# Edge-Lit_Clock_v3_1.net
KiCad netlist of a schematic drawn in EAGLE
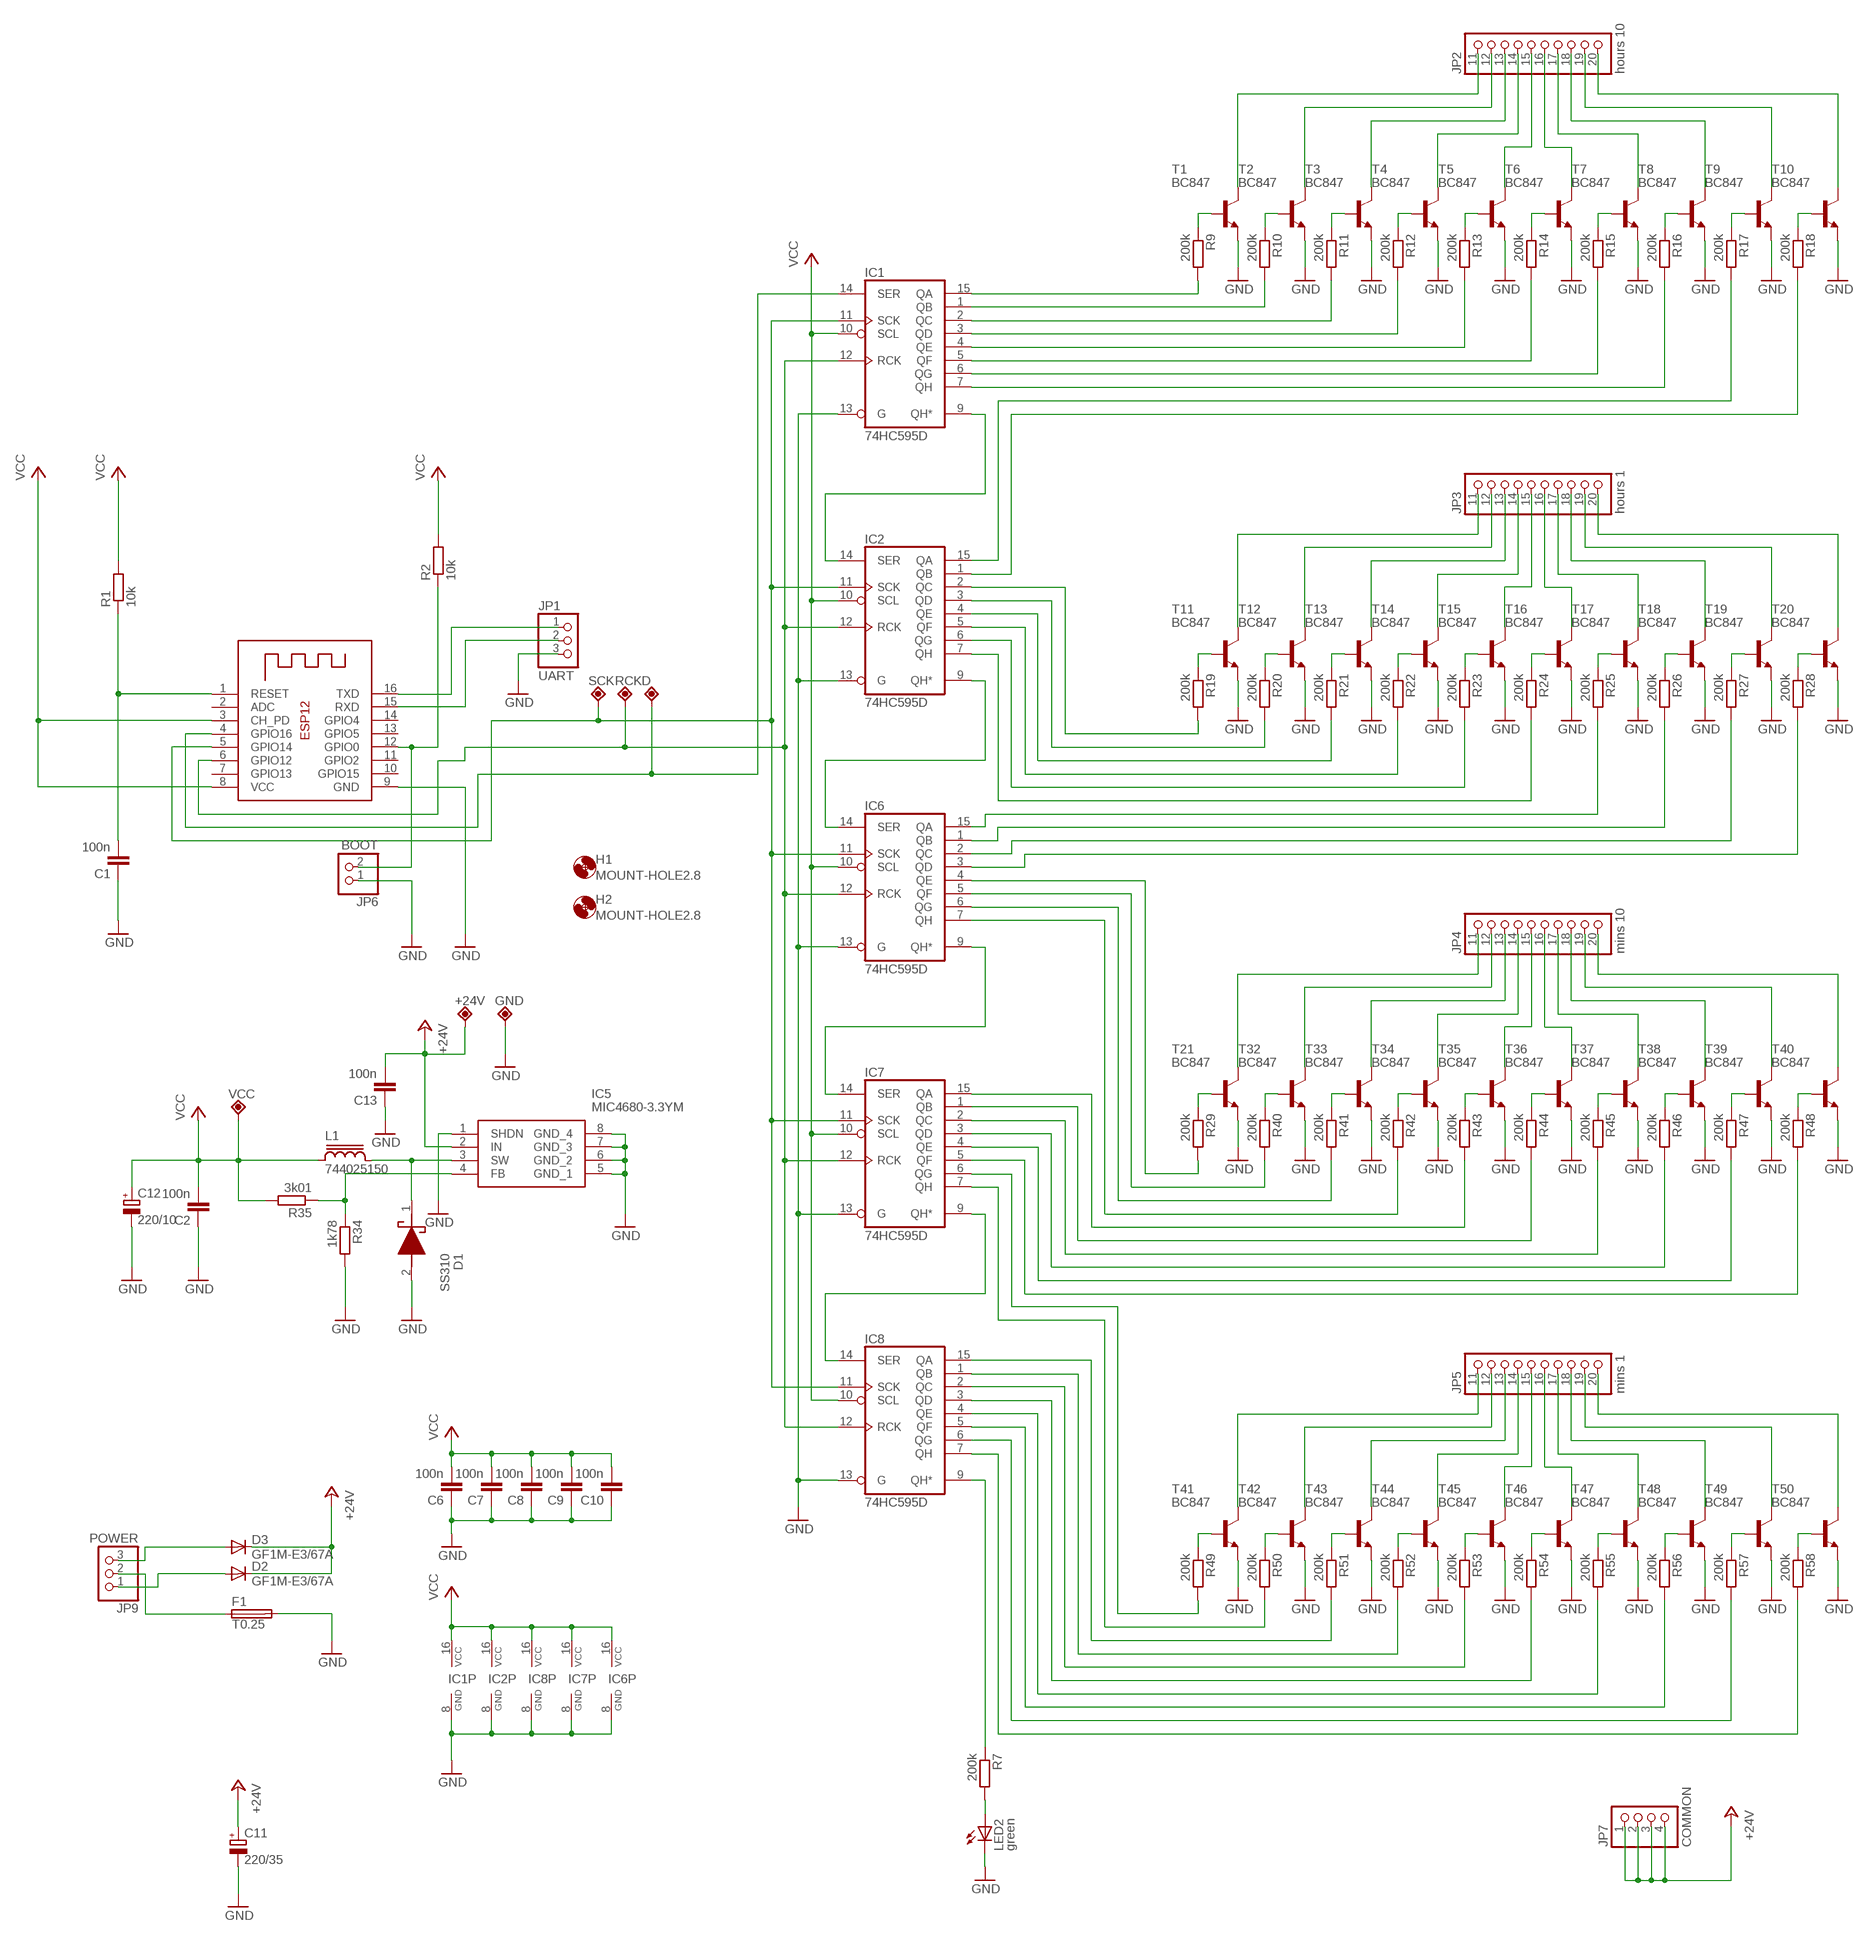
[diagram p0: schematic, sheet 1]

(export (version "E")
  (design (tool "Eeschema 10.0.6"))
  (components
    (comp (ref "+24V")
      (value "TPP-PAD-024")
      (footprint "eagle-import:PAD-024")
      (libsource (lib "eagle-import") (part "TPP-PAD-024"))
    )
    (comp (ref "C1")
      (value "100n")
      (footprint "eagle-import:C0805")
      (libsource (lib "eagle-import") (part "C-EUC0805"))
    )
    (comp (ref "C2")
      (value "100n")
      (footprint "eagle-import:C0805")
      (libsource (lib "eagle-import") (part "C-EUC0805"))
    )
    (comp (ref "C6")
      (value "100n")
      (footprint "eagle-import:C0805")
      (libsource (lib "eagle-import") (part "C-EUC0805"))
    )
    (comp (ref "C7")
      (value "100n")
      (footprint "eagle-import:C0805")
      (libsource (lib "eagle-import") (part "C-EUC0805"))
    )
    (comp (ref "C8")
      (value "100n")
      (footprint "eagle-import:C0805")
      (libsource (lib "eagle-import") (part "C-EUC0805"))
    )
    (comp (ref "C9")
      (value "100n")
      (footprint "eagle-import:C0805")
      (libsource (lib "eagle-import") (part "C-EUC0805"))
    )
    (comp (ref "C10")
      (value "100n")
      (footprint "eagle-import:C0805")
      (libsource (lib "eagle-import") (part "C-EUC0805"))
    )
    (comp (ref "C11")
      (value "220/35")
      (footprint "eagle-import:SANYO-OSCON_SMD_E7")
      (libsource (lib "eagle-import") (part "CPOL-EUSANYO_SMD_E7"))
    )
    (comp (ref "C12")
      (value "220/10")
      (footprint "eagle-import:SANYO-OSCON_SMD_E7")
      (libsource (lib "eagle-import") (part "CPOL-EUSANYO_SMD_E7"))
    )
    (comp (ref "C13")
      (value "100n")
      (footprint "eagle-import:C0805")
      (libsource (lib "eagle-import") (part "C-EUC0805"))
    )
    (comp (ref "D")
      (value "TPP-PAD-024")
      (footprint "eagle-import:PAD-024")
      (libsource (lib "eagle-import") (part "TPP-PAD-024"))
    )
    (comp (ref "D1")
      (value "SS310")
      (footprint "eagle-import:DIOM7959X262N")
      (fields (field (name "MOUSER_PART_NUMBER") "821-SS310"))
      (libsource (lib "eagle-import") (part "SS310"))
    )
    (comp (ref "D2")
      (value "GF1M-E3/67A")
      (footprint "eagle-import:DO214BA")
      (libsource (lib "eagle-import") (part "DIODE-DO214BA"))
    )
    (comp (ref "D3")
      (value "GF1M-E3/67A")
      (footprint "eagle-import:DO214BA")
      (libsource (lib "eagle-import") (part "DIODE-DO214BA"))
    )
    (comp (ref "F1")
      (value "T0.25")
      (footprint "eagle-import:TE5")
      (libsource (lib "eagle-import") (part "TE5"))
    )
    (comp (ref "GND")
      (value "TPP-PAD-024")
      (footprint "eagle-import:PAD-024")
      (libsource (lib "eagle-import") (part "TPP-PAD-024"))
    )
    (comp (ref "H1")
      (value "MOUNT-HOLE2.8")
      (footprint "eagle-import:2,8")
      (libsource (lib "eagle-import") (part "MOUNT-HOLE2.8"))
    )
    (comp (ref "H2")
      (value "MOUNT-HOLE2.8")
      (footprint "eagle-import:2,8")
      (libsource (lib "eagle-import") (part "MOUNT-HOLE2.8"))
    )
    (comp (ref "IC1")
      (value "74HC595D")
      (footprint "eagle-import:SO16")
      (libsource (lib "eagle-import") (part "74595DHC"))
    )
    (comp (ref "IC2")
      (value "74HC595D")
      (footprint "eagle-import:SO16")
      (libsource (lib "eagle-import") (part "74595DHC"))
    )
    (comp (ref "IC5")
      (value "MIC4680-3.3YM")
      (footprint "eagle-import:SOIC127P599X173-8N")
      (fields (field (name "MOUSER_PART_NUMBER") "998-MIC4680-3.3YM"))
      (libsource (lib "eagle-import") (part "MIC4680-3.3YM"))
    )
    (comp (ref "IC6")
      (value "74HC595D")
      (footprint "eagle-import:SO16")
      (libsource (lib "eagle-import") (part "74595DHC"))
    )
    (comp (ref "IC7")
      (value "74HC595D")
      (footprint "eagle-import:SO16")
      (libsource (lib "eagle-import") (part "74595DHC"))
    )
    (comp (ref "IC8")
      (value "74HC595D")
      (footprint "eagle-import:SO16")
      (libsource (lib "eagle-import") (part "74595DHC"))
    )
    (comp (ref "JP1")
      (value "UART")
      (footprint "eagle-import:1X03")
      (libsource (lib "eagle-import") (part "PINHD-1X3"))
    )
    (comp (ref "JP2")
      (value "hours 10")
      (footprint "eagle-import:1X10")
      (libsource (lib "eagle-import") (part "PINHD-1X10"))
    )
    (comp (ref "JP3")
      (value "hours 1")
      (footprint "eagle-import:1X10")
      (libsource (lib "eagle-import") (part "PINHD-1X10"))
    )
    (comp (ref "JP4")
      (value "mins 10")
      (footprint "eagle-import:1X10")
      (libsource (lib "eagle-import") (part "PINHD-1X10"))
    )
    (comp (ref "JP5")
      (value "mins 1")
      (footprint "eagle-import:1X10")
      (libsource (lib "eagle-import") (part "PINHD-1X10"))
    )
    (comp (ref "JP6")
      (value "BOOT")
      (footprint "eagle-import:1X02")
      (libsource (lib "eagle-import") (part "PINHD-1X2"))
    )
    (comp (ref "JP7")
      (value "COMMON")
      (footprint "eagle-import:1X04")
      (libsource (lib "eagle-import") (part "PINHD-1X4"))
    )
    (comp (ref "JP9")
      (value "POWER")
      (footprint "eagle-import:1X03")
      (libsource (lib "eagle-import") (part "PINHD-1X3"))
    )
    (comp (ref "L1")
      (value "744025150")
      (footprint "eagle-import:744025150")
      (libsource (lib "eagle-import") (part "744025150"))
    )
    (comp (ref "LED2")
      (value "green")
      (footprint "eagle-import:SML0805")
      (libsource (lib "eagle-import") (part "LEDSML0805"))
    )
    (comp (ref "R1")
      (value "10k")
      (footprint "eagle-import:M0805")
      (libsource (lib "eagle-import") (part "R-EU_M0805"))
    )
    (comp (ref "R2")
      (value "10k")
      (footprint "eagle-import:M0805")
      (libsource (lib "eagle-import") (part "R-EU_M0805"))
    )
    (comp (ref "R7")
      (value "200k")
      (footprint "eagle-import:M0805")
      (libsource (lib "eagle-import") (part "R-EU_M0805"))
    )
    (comp (ref "R9")
      (value "200k")
      (footprint "eagle-import:M0805")
      (libsource (lib "eagle-import") (part "R-EU_M0805"))
    )
    (comp (ref "R10")
      (value "200k")
      (footprint "eagle-import:M0805")
      (libsource (lib "eagle-import") (part "R-EU_M0805"))
    )
    (comp (ref "R11")
      (value "200k")
      (footprint "eagle-import:M0805")
      (libsource (lib "eagle-import") (part "R-EU_M0805"))
    )
    (comp (ref "R12")
      (value "200k")
      (footprint "eagle-import:M0805")
      (libsource (lib "eagle-import") (part "R-EU_M0805"))
    )
    (comp (ref "R13")
      (value "200k")
      (footprint "eagle-import:M0805")
      (libsource (lib "eagle-import") (part "R-EU_M0805"))
    )
    (comp (ref "R14")
      (value "200k")
      (footprint "eagle-import:M0805")
      (libsource (lib "eagle-import") (part "R-EU_M0805"))
    )
    (comp (ref "R15")
      (value "200k")
      (footprint "eagle-import:M0805")
      (libsource (lib "eagle-import") (part "R-EU_M0805"))
    )
    (comp (ref "R16")
      (value "200k")
      (footprint "eagle-import:M0805")
      (libsource (lib "eagle-import") (part "R-EU_M0805"))
    )
    (comp (ref "R17")
      (value "200k")
      (footprint "eagle-import:M0805")
      (libsource (lib "eagle-import") (part "R-EU_M0805"))
    )
    (comp (ref "R18")
      (value "200k")
      (footprint "eagle-import:M0805")
      (libsource (lib "eagle-import") (part "R-EU_M0805"))
    )
    (comp (ref "R19")
      (value "200k")
      (footprint "eagle-import:M0805")
      (libsource (lib "eagle-import") (part "R-EU_M0805"))
    )
    (comp (ref "R20")
      (value "200k")
      (footprint "eagle-import:M0805")
      (libsource (lib "eagle-import") (part "R-EU_M0805"))
    )
    (comp (ref "R21")
      (value "200k")
      (footprint "eagle-import:M0805")
      (libsource (lib "eagle-import") (part "R-EU_M0805"))
    )
    (comp (ref "R22")
      (value "200k")
      (footprint "eagle-import:M0805")
      (libsource (lib "eagle-import") (part "R-EU_M0805"))
    )
    (comp (ref "R23")
      (value "200k")
      (footprint "eagle-import:M0805")
      (libsource (lib "eagle-import") (part "R-EU_M0805"))
    )
    (comp (ref "R24")
      (value "200k")
      (footprint "eagle-import:M0805")
      (libsource (lib "eagle-import") (part "R-EU_M0805"))
    )
    (comp (ref "R25")
      (value "200k")
      (footprint "eagle-import:M0805")
      (libsource (lib "eagle-import") (part "R-EU_M0805"))
    )
    (comp (ref "R26")
      (value "200k")
      (footprint "eagle-import:M0805")
      (libsource (lib "eagle-import") (part "R-EU_M0805"))
    )
    (comp (ref "R27")
      (value "200k")
      (footprint "eagle-import:M0805")
      (libsource (lib "eagle-import") (part "R-EU_M0805"))
    )
    (comp (ref "R28")
      (value "200k")
      (footprint "eagle-import:M0805")
      (libsource (lib "eagle-import") (part "R-EU_M0805"))
    )
    (comp (ref "R29")
      (value "200k")
      (footprint "eagle-import:M0805")
      (libsource (lib "eagle-import") (part "R-EU_M0805"))
    )
    (comp (ref "R34")
      (value "1k78")
      (footprint "eagle-import:M0805")
      (libsource (lib "eagle-import") (part "R-EU_M0805"))
    )
    (comp (ref "R35")
      (value "3k01")
      (footprint "eagle-import:M0805")
      (libsource (lib "eagle-import") (part "R-EU_M0805"))
    )
    (comp (ref "R40")
      (value "200k")
      (footprint "eagle-import:M0805")
      (libsource (lib "eagle-import") (part "R-EU_M0805"))
    )
    (comp (ref "R41")
      (value "200k")
      (footprint "eagle-import:M0805")
      (libsource (lib "eagle-import") (part "R-EU_M0805"))
    )
    (comp (ref "R42")
      (value "200k")
      (footprint "eagle-import:M0805")
      (libsource (lib "eagle-import") (part "R-EU_M0805"))
    )
    (comp (ref "R43")
      (value "200k")
      (footprint "eagle-import:M0805")
      (libsource (lib "eagle-import") (part "R-EU_M0805"))
    )
    (comp (ref "R44")
      (value "200k")
      (footprint "eagle-import:M0805")
      (libsource (lib "eagle-import") (part "R-EU_M0805"))
    )
    (comp (ref "R45")
      (value "200k")
      (footprint "eagle-import:M0805")
      (libsource (lib "eagle-import") (part "R-EU_M0805"))
    )
    (comp (ref "R46")
      (value "200k")
      (footprint "eagle-import:M0805")
      (libsource (lib "eagle-import") (part "R-EU_M0805"))
    )
    (comp (ref "R47")
      (value "200k")
      (footprint "eagle-import:M0805")
      (libsource (lib "eagle-import") (part "R-EU_M0805"))
    )
    (comp (ref "R48")
      (value "200k")
      (footprint "eagle-import:M0805")
      (libsource (lib "eagle-import") (part "R-EU_M0805"))
    )
    (comp (ref "R49")
      (value "200k")
      (footprint "eagle-import:M0805")
      (libsource (lib "eagle-import") (part "R-EU_M0805"))
    )
    (comp (ref "R50")
      (value "200k")
      (footprint "eagle-import:M0805")
      (libsource (lib "eagle-import") (part "R-EU_M0805"))
    )
    (comp (ref "R51")
      (value "200k")
      (footprint "eagle-import:M0805")
      (libsource (lib "eagle-import") (part "R-EU_M0805"))
    )
    (comp (ref "R52")
      (value "200k")
      (footprint "eagle-import:M0805")
      (libsource (lib "eagle-import") (part "R-EU_M0805"))
    )
    (comp (ref "R53")
      (value "200k")
      (footprint "eagle-import:M0805")
      (libsource (lib "eagle-import") (part "R-EU_M0805"))
    )
    (comp (ref "R54")
      (value "200k")
      (footprint "eagle-import:M0805")
      (libsource (lib "eagle-import") (part "R-EU_M0805"))
    )
    (comp (ref "R55")
      (value "200k")
      (footprint "eagle-import:M0805")
      (libsource (lib "eagle-import") (part "R-EU_M0805"))
    )
    (comp (ref "R56")
      (value "200k")
      (footprint "eagle-import:M0805")
      (libsource (lib "eagle-import") (part "R-EU_M0805"))
    )
    (comp (ref "R57")
      (value "200k")
      (footprint "eagle-import:M0805")
      (libsource (lib "eagle-import") (part "R-EU_M0805"))
    )
    (comp (ref "R58")
      (value "200k")
      (footprint "eagle-import:M0805")
      (libsource (lib "eagle-import") (part "R-EU_M0805"))
    )
    (comp (ref "RCK")
      (value "TPP-PAD-024")
      (footprint "eagle-import:PAD-024")
      (libsource (lib "eagle-import") (part "TPP-PAD-024"))
    )
    (comp (ref "SCK")
      (value "TPP-PAD-024")
      (footprint "eagle-import:PAD-024")
      (libsource (lib "eagle-import") (part "TPP-PAD-024"))
    )
    (comp (ref "T1")
      (value "BC847")
      (footprint "eagle-import:SOT23")
      (libsource (lib "eagle-import") (part "BC847"))
    )
    (comp (ref "T2")
      (value "BC847")
      (footprint "eagle-import:SOT23")
      (libsource (lib "eagle-import") (part "BC847"))
    )
    (comp (ref "T3")
      (value "BC847")
      (footprint "eagle-import:SOT23")
      (libsource (lib "eagle-import") (part "BC847"))
    )
    (comp (ref "T4")
      (value "BC847")
      (footprint "eagle-import:SOT23")
      (libsource (lib "eagle-import") (part "BC847"))
    )
    (comp (ref "T5")
      (value "BC847")
      (footprint "eagle-import:SOT23")
      (libsource (lib "eagle-import") (part "BC847"))
    )
    (comp (ref "T6")
      (value "BC847")
      (footprint "eagle-import:SOT23")
      (libsource (lib "eagle-import") (part "BC847"))
    )
    (comp (ref "T7")
      (value "BC847")
      (footprint "eagle-import:SOT23")
      (libsource (lib "eagle-import") (part "BC847"))
    )
    (comp (ref "T8")
      (value "BC847")
      (footprint "eagle-import:SOT23")
      (libsource (lib "eagle-import") (part "BC847"))
    )
    (comp (ref "T9")
      (value "BC847")
      (footprint "eagle-import:SOT23")
      (libsource (lib "eagle-import") (part "BC847"))
    )
    (comp (ref "T10")
      (value "BC847")
      (footprint "eagle-import:SOT23")
      (libsource (lib "eagle-import") (part "BC847"))
    )
    (comp (ref "T11")
      (value "BC847")
      (footprint "eagle-import:SOT23")
      (libsource (lib "eagle-import") (part "BC847"))
    )
    (comp (ref "T12")
      (value "BC847")
      (footprint "eagle-import:SOT23")
      (libsource (lib "eagle-import") (part "BC847"))
    )
    (comp (ref "T13")
      (value "BC847")
      (footprint "eagle-import:SOT23")
      (libsource (lib "eagle-import") (part "BC847"))
    )
    (comp (ref "T14")
      (value "BC847")
      (footprint "eagle-import:SOT23")
      (libsource (lib "eagle-import") (part "BC847"))
    )
    (comp (ref "T15")
      (value "BC847")
      (footprint "eagle-import:SOT23")
      (libsource (lib "eagle-import") (part "BC847"))
    )
    (comp (ref "T16")
      (value "BC847")
      (footprint "eagle-import:SOT23")
      (libsource (lib "eagle-import") (part "BC847"))
    )
    (comp (ref "T17")
      (value "BC847")
      (footprint "eagle-import:SOT23")
      (libsource (lib "eagle-import") (part "BC847"))
    )
    (comp (ref "T18")
      (value "BC847")
      (footprint "eagle-import:SOT23")
      (libsource (lib "eagle-import") (part "BC847"))
    )
    (comp (ref "T19")
      (value "BC847")
      (footprint "eagle-import:SOT23")
      (libsource (lib "eagle-import") (part "BC847"))
    )
    (comp (ref "T20")
      (value "BC847")
      (footprint "eagle-import:SOT23")
      (libsource (lib "eagle-import") (part "BC847"))
    )
    (comp (ref "T21")
      (value "BC847")
      (footprint "eagle-import:SOT23")
      (libsource (lib "eagle-import") (part "BC847"))
    )
    (comp (ref "T32")
      (value "BC847")
      (footprint "eagle-import:SOT23")
      (libsource (lib "eagle-import") (part "BC847"))
    )
    (comp (ref "T33")
      (value "BC847")
      (footprint "eagle-import:SOT23")
      (libsource (lib "eagle-import") (part "BC847"))
    )
    (comp (ref "T34")
      (value "BC847")
      (footprint "eagle-import:SOT23")
      (libsource (lib "eagle-import") (part "BC847"))
    )
    (comp (ref "T35")
      (value "BC847")
      (footprint "eagle-import:SOT23")
      (libsource (lib "eagle-import") (part "BC847"))
    )
    (comp (ref "T36")
      (value "BC847")
      (footprint "eagle-import:SOT23")
      (libsource (lib "eagle-import") (part "BC847"))
    )
    (comp (ref "T37")
      (value "BC847")
      (footprint "eagle-import:SOT23")
      (libsource (lib "eagle-import") (part "BC847"))
    )
    (comp (ref "T38")
      (value "BC847")
      (footprint "eagle-import:SOT23")
      (libsource (lib "eagle-import") (part "BC847"))
    )
    (comp (ref "T39")
      (value "BC847")
      (footprint "eagle-import:SOT23")
      (libsource (lib "eagle-import") (part "BC847"))
    )
    (comp (ref "T40")
      (value "BC847")
      (footprint "eagle-import:SOT23")
      (libsource (lib "eagle-import") (part "BC847"))
    )
    (comp (ref "T41")
      (value "BC847")
      (footprint "eagle-import:SOT23")
      (libsource (lib "eagle-import") (part "BC847"))
    )
    (comp (ref "T42")
      (value "BC847")
      (footprint "eagle-import:SOT23")
      (libsource (lib "eagle-import") (part "BC847"))
    )
    (comp (ref "T43")
      (value "BC847")
      (footprint "eagle-import:SOT23")
      (libsource (lib "eagle-import") (part "BC847"))
    )
    (comp (ref "T44")
      (value "BC847")
      (footprint "eagle-import:SOT23")
      (libsource (lib "eagle-import") (part "BC847"))
    )
    (comp (ref "T45")
      (value "BC847")
      (footprint "eagle-import:SOT23")
      (libsource (lib "eagle-import") (part "BC847"))
    )
    (comp (ref "T46")
      (value "BC847")
      (footprint "eagle-import:SOT23")
      (libsource (lib "eagle-import") (part "BC847"))
    )
    (comp (ref "T47")
      (value "BC847")
      (footprint "eagle-import:SOT23")
      (libsource (lib "eagle-import") (part "BC847"))
    )
    (comp (ref "T48")
      (value "BC847")
      (footprint "eagle-import:SOT23")
      (libsource (lib "eagle-import") (part "BC847"))
    )
    (comp (ref "T49")
      (value "BC847")
      (footprint "eagle-import:SOT23")
      (libsource (lib "eagle-import") (part "BC847"))
    )
    (comp (ref "T50")
      (value "BC847")
      (footprint "eagle-import:SOT23")
      (libsource (lib "eagle-import") (part "BC847"))
    )
    (comp (ref "VCC")
      (value "TPP-PAD-024")
      (footprint "eagle-import:PAD-024")
      (libsource (lib "eagle-import") (part "TPP-PAD-024"))
    )
    (comp (ref "X1")
      (value "ESP12")
      (footprint "eagle-import:ESP-12")
      (libsource (lib "eagle-import") (part "ESP-12"))
    )
  )
  (nets
    (net (code "1") (name "+24V") (class "Default")
      (node (ref "+24V") (pin "1") (pinfunction "P_1") (pintype "passive"))
      (node (ref "C11") (pin "+") (pinfunction "+_+") (pintype "passive"))
      (node (ref "C13") (pin "2") (pinfunction "2_2") (pintype "passive"))
      (node (ref "D2") (pin "C") (pinfunction "C_C") (pintype "passive"))
      (node (ref "D3") (pin "C") (pinfunction "C_C") (pintype "passive"))
      (node (ref "IC5") (pin "2") (pinfunction "IN_2") (pintype "bidirectional"))
      (node (ref "JP7") (pin "1") (pinfunction "1_1") (pintype "passive"))
      (node (ref "JP7") (pin "2") (pinfunction "2_2") (pintype "passive"))
      (node (ref "JP7") (pin "3") (pinfunction "3_3") (pintype "passive"))
      (node (ref "JP7") (pin "4") (pinfunction "4_4") (pintype "passive"))
    )
    (net (code "2") (name "GND") (class "Default")
      (node (ref "C1") (pin "1") (pinfunction "1_1") (pintype "passive"))
      (node (ref "C10") (pin "1") (pinfunction "1_1") (pintype "passive"))
      (node (ref "C11") (pin "-") (pinfunction "-_-") (pintype "passive"))
      (node (ref "C12") (pin "-") (pinfunction "-_-") (pintype "passive"))
      (node (ref "C13") (pin "1") (pinfunction "1_1") (pintype "passive"))
      (node (ref "C2") (pin "1") (pinfunction "1_1") (pintype "passive"))
      (node (ref "C6") (pin "1") (pinfunction "1_1") (pintype "passive"))
      (node (ref "C7") (pin "1") (pinfunction "1_1") (pintype "passive"))
      (node (ref "C8") (pin "1") (pinfunction "1_1") (pintype "passive"))
      (node (ref "C9") (pin "1") (pinfunction "1_1") (pintype "passive"))
      (node (ref "D1") (pin "2") (pinfunction "A_2") (pintype "bidirectional"))
      (node (ref "F1") (pin "2") (pinfunction "2_2") (pintype "passive"))
      (node (ref "GND") (pin "1") (pinfunction "P_1") (pintype "passive"))
      (node (ref "IC1") (pin "13") (pinfunction "G_13") (pintype "input"))
      (node (ref "IC1") (pin "8") (pinfunction "GND_8") (pintype "power_in"))
      (node (ref "IC2") (pin "13") (pinfunction "G_13") (pintype "input"))
      (node (ref "IC2") (pin "8") (pinfunction "GND_8") (pintype "power_in"))
      (node (ref "IC5") (pin "1") (pinfunction "SHDN_1") (pintype "bidirectional"))
      (node (ref "IC5") (pin "5") (pinfunction "GND_1_5") (pintype "bidirectional"))
      (node (ref "IC5") (pin "6") (pinfunction "GND_2_6") (pintype "bidirectional"))
      (node (ref "IC5") (pin "7") (pinfunction "GND_3_7") (pintype "bidirectional"))
      (node (ref "IC5") (pin "8") (pinfunction "GND_4_8") (pintype "bidirectional"))
      (node (ref "IC6") (pin "13") (pinfunction "G_13") (pintype "input"))
      (node (ref "IC6") (pin "8") (pinfunction "GND_8") (pintype "power_in"))
      (node (ref "IC7") (pin "13") (pinfunction "G_13") (pintype "input"))
      (node (ref "IC7") (pin "8") (pinfunction "GND_8") (pintype "power_in"))
      (node (ref "IC8") (pin "13") (pinfunction "G_13") (pintype "input"))
      (node (ref "IC8") (pin "8") (pinfunction "GND_8") (pintype "power_in"))
      (node (ref "JP1") (pin "3") (pinfunction "3_3") (pintype "passive"))
      (node (ref "JP6") (pin "1") (pinfunction "1_1") (pintype "passive"))
      (node (ref "LED2") (pin "C") (pinfunction "C_C") (pintype "passive"))
      (node (ref "R34") (pin "2") (pinfunction "2_2") (pintype "passive"))
      (node (ref "T1") (pin "2") (pinfunction "E_2") (pintype "passive"))
      (node (ref "T10") (pin "2") (pinfunction "E_2") (pintype "passive"))
      (node (ref "T11") (pin "2") (pinfunction "E_2") (pintype "passive"))
      (node (ref "T12") (pin "2") (pinfunction "E_2") (pintype "passive"))
      (node (ref "T13") (pin "2") (pinfunction "E_2") (pintype "passive"))
      (node (ref "T14") (pin "2") (pinfunction "E_2") (pintype "passive"))
      (node (ref "T15") (pin "2") (pinfunction "E_2") (pintype "passive"))
      (node (ref "T16") (pin "2") (pinfunction "E_2") (pintype "passive"))
      (node (ref "T17") (pin "2") (pinfunction "E_2") (pintype "passive"))
      (node (ref "T18") (pin "2") (pinfunction "E_2") (pintype "passive"))
      (node (ref "T19") (pin "2") (pinfunction "E_2") (pintype "passive"))
      (node (ref "T2") (pin "2") (pinfunction "E_2") (pintype "passive"))
      (node (ref "T20") (pin "2") (pinfunction "E_2") (pintype "passive"))
      (node (ref "T21") (pin "2") (pinfunction "E_2") (pintype "passive"))
      (node (ref "T3") (pin "2") (pinfunction "E_2") (pintype "passive"))
      (node (ref "T32") (pin "2") (pinfunction "E_2") (pintype "passive"))
      (node (ref "T33") (pin "2") (pinfunction "E_2") (pintype "passive"))
      (node (ref "T34") (pin "2") (pinfunction "E_2") (pintype "passive"))
      (node (ref "T35") (pin "2") (pinfunction "E_2") (pintype "passive"))
      (node (ref "T36") (pin "2") (pinfunction "E_2") (pintype "passive"))
      (node (ref "T37") (pin "2") (pinfunction "E_2") (pintype "passive"))
      (node (ref "T38") (pin "2") (pinfunction "E_2") (pintype "passive"))
      (node (ref "T39") (pin "2") (pinfunction "E_2") (pintype "passive"))
      (node (ref "T4") (pin "2") (pinfunction "E_2") (pintype "passive"))
      (node (ref "T40") (pin "2") (pinfunction "E_2") (pintype "passive"))
      (node (ref "T41") (pin "2") (pinfunction "E_2") (pintype "passive"))
      (node (ref "T42") (pin "2") (pinfunction "E_2") (pintype "passive"))
      (node (ref "T43") (pin "2") (pinfunction "E_2") (pintype "passive"))
      (node (ref "T44") (pin "2") (pinfunction "E_2") (pintype "passive"))
      (node (ref "T45") (pin "2") (pinfunction "E_2") (pintype "passive"))
      (node (ref "T46") (pin "2") (pinfunction "E_2") (pintype "passive"))
      (node (ref "T47") (pin "2") (pinfunction "E_2") (pintype "passive"))
      (node (ref "T48") (pin "2") (pinfunction "E_2") (pintype "passive"))
      (node (ref "T49") (pin "2") (pinfunction "E_2") (pintype "passive"))
      (node (ref "T5") (pin "2") (pinfunction "E_2") (pintype "passive"))
      (node (ref "T50") (pin "2") (pinfunction "E_2") (pintype "passive"))
      (node (ref "T6") (pin "2") (pinfunction "E_2") (pintype "passive"))
      (node (ref "T7") (pin "2") (pinfunction "E_2") (pintype "passive"))
      (node (ref "T8") (pin "2") (pinfunction "E_2") (pintype "passive"))
      (node (ref "T9") (pin "2") (pinfunction "E_2") (pintype "passive"))
      (node (ref "X1") (pin "9") (pinfunction "GND_9") (pintype "power_in"))
    )
    (net (code "3") (name "Net-(D-P)") (class "Default")
      (node (ref "D") (pin "1") (pinfunction "P_1") (pintype "passive"))
      (node (ref "IC1") (pin "14") (pinfunction "SER_14") (pintype "input"))
      (node (ref "X1") (pin "4") (pinfunction "GPIO16_4") (pintype "bidirectional"))
    )
    (net (code "4") (name "Net-(D1-K)") (class "Default")
      (node (ref "D1") (pin "1") (pinfunction "K_1") (pintype "bidirectional"))
      (node (ref "IC5") (pin "3") (pinfunction "SW_3") (pintype "bidirectional"))
      (node (ref "L1") (pin "2") (pinfunction "2_2") (pintype "passive"))
    )
    (net (code "5") (name "Net-(D2-PadA)") (class "Default")
      (node (ref "D2") (pin "A") (pinfunction "A_A") (pintype "passive"))
      (node (ref "JP9") (pin "1") (pinfunction "1_1") (pintype "passive"))
    )
    (net (code "6") (name "Net-(D3-PadA)") (class "Default")
      (node (ref "D3") (pin "A") (pinfunction "A_A") (pintype "passive"))
      (node (ref "JP9") (pin "3") (pinfunction "3_3") (pintype "passive"))
    )
    (net (code "7") (name "Net-(F1-Pad1)") (class "Default")
      (node (ref "F1") (pin "1") (pinfunction "1_1") (pintype "passive"))
      (node (ref "JP9") (pin "2") (pinfunction "2_2") (pintype "passive"))
    )
    (net (code "8") (name "Net-(IC1A-QA)") (class "Default")
      (node (ref "IC1") (pin "15") (pinfunction "QA_15") (pintype "tri_state"))
      (node (ref "R9") (pin "2") (pinfunction "2_2") (pintype "passive"))
    )
    (net (code "9") (name "Net-(IC1A-QB)") (class "Default")
      (node (ref "IC1") (pin "1") (pinfunction "QB_1") (pintype "tri_state"))
      (node (ref "R10") (pin "2") (pinfunction "2_2") (pintype "passive"))
    )
    (net (code "10") (name "Net-(IC1A-QC)") (class "Default")
      (node (ref "IC1") (pin "2") (pinfunction "QC_2") (pintype "tri_state"))
      (node (ref "R11") (pin "2") (pinfunction "2_2") (pintype "passive"))
    )
    (net (code "11") (name "Net-(IC1A-QD)") (class "Default")
      (node (ref "IC1") (pin "3") (pinfunction "QD_3") (pintype "tri_state"))
      (node (ref "R12") (pin "2") (pinfunction "2_2") (pintype "passive"))
    )
    (net (code "12") (name "Net-(IC1A-QE)") (class "Default")
      (node (ref "IC1") (pin "4") (pinfunction "QE_4") (pintype "tri_state"))
      (node (ref "R13") (pin "2") (pinfunction "2_2") (pintype "passive"))
    )
    (net (code "13") (name "Net-(IC1A-QF)") (class "Default")
      (node (ref "IC1") (pin "5") (pinfunction "QF_5") (pintype "tri_state"))
      (node (ref "R14") (pin "2") (pinfunction "2_2") (pintype "passive"))
    )
    (net (code "14") (name "Net-(IC1A-QG)") (class "Default")
      (node (ref "IC1") (pin "6") (pinfunction "QG_6") (pintype "tri_state"))
      (node (ref "R15") (pin "2") (pinfunction "2_2") (pintype "passive"))
    )
    (net (code "15") (name "Net-(IC1A-QH)") (class "Default")
      (node (ref "IC1") (pin "7") (pinfunction "QH_7") (pintype "tri_state"))
      (node (ref "R16") (pin "2") (pinfunction "2_2") (pintype "passive"))
    )
    (net (code "16") (name "Net-(IC1A-QH*)") (class "Default")
      (node (ref "IC1") (pin "9") (pinfunction "QH*_9") (pintype "tri_state"))
      (node (ref "IC2") (pin "14") (pinfunction "SER_14") (pintype "input"))
    )
    (net (code "17") (name "Net-(IC1A-RCK)") (class "Default")
      (node (ref "IC1") (pin "12") (pinfunction "RCK_12") (pintype "input"))
      (node (ref "IC2") (pin "12") (pinfunction "RCK_12") (pintype "input"))
      (node (ref "IC6") (pin "12") (pinfunction "RCK_12") (pintype "input"))
      (node (ref "IC7") (pin "12") (pinfunction "RCK_12") (pintype "input"))
      (node (ref "IC8") (pin "12") (pinfunction "RCK_12") (pintype "input"))
      (node (ref "RCK") (pin "1") (pinfunction "P_1") (pintype "passive"))
      (node (ref "X1") (pin "6") (pinfunction "GPIO12_6") (pintype "bidirectional"))
    )
    (net (code "18") (name "Net-(IC1A-SCK)") (class "Default")
      (node (ref "IC1") (pin "11") (pinfunction "SCK_11") (pintype "input"))
      (node (ref "IC2") (pin "11") (pinfunction "SCK_11") (pintype "input"))
      (node (ref "IC6") (pin "11") (pinfunction "SCK_11") (pintype "input"))
      (node (ref "IC7") (pin "11") (pinfunction "SCK_11") (pintype "input"))
      (node (ref "IC8") (pin "11") (pinfunction "SCK_11") (pintype "input"))
      (node (ref "SCK") (pin "1") (pinfunction "P_1") (pintype "passive"))
      (node (ref "X1") (pin "5") (pinfunction "GPIO14_5") (pintype "bidirectional"))
    )
    (net (code "19") (name "Net-(IC2A-QA)") (class "Default")
      (node (ref "IC2") (pin "15") (pinfunction "QA_15") (pintype "tri_state"))
      (node (ref "R17") (pin "2") (pinfunction "2_2") (pintype "passive"))
    )
    (net (code "20") (name "Net-(IC2A-QB)") (class "Default")
      (node (ref "IC2") (pin "1") (pinfunction "QB_1") (pintype "tri_state"))
      (node (ref "R18") (pin "2") (pinfunction "2_2") (pintype "passive"))
    )
    (net (code "21") (name "Net-(IC2A-QC)") (class "Default")
      (node (ref "IC2") (pin "2") (pinfunction "QC_2") (pintype "tri_state"))
      (node (ref "R19") (pin "2") (pinfunction "2_2") (pintype "passive"))
    )
    (net (code "22") (name "Net-(IC2A-QD)") (class "Default")
      (node (ref "IC2") (pin "3") (pinfunction "QD_3") (pintype "tri_state"))
      (node (ref "R20") (pin "2") (pinfunction "2_2") (pintype "passive"))
    )
    (net (code "23") (name "Net-(IC2A-QE)") (class "Default")
      (node (ref "IC2") (pin "4") (pinfunction "QE_4") (pintype "tri_state"))
      (node (ref "R21") (pin "2") (pinfunction "2_2") (pintype "passive"))
    )
    (net (code "24") (name "Net-(IC2A-QF)") (class "Default")
      (node (ref "IC2") (pin "5") (pinfunction "QF_5") (pintype "tri_state"))
      (node (ref "R22") (pin "2") (pinfunction "2_2") (pintype "passive"))
    )
    (net (code "25") (name "Net-(IC2A-QG)") (class "Default")
      (node (ref "IC2") (pin "6") (pinfunction "QG_6") (pintype "tri_state"))
      (node (ref "R23") (pin "2") (pinfunction "2_2") (pintype "passive"))
    )
    (net (code "26") (name "Net-(IC2A-QH)") (class "Default")
      (node (ref "IC2") (pin "7") (pinfunction "QH_7") (pintype "tri_state"))
      (node (ref "R24") (pin "2") (pinfunction "2_2") (pintype "passive"))
    )
    (net (code "27") (name "Net-(IC2A-QH*)") (class "Default")
      (node (ref "IC2") (pin "9") (pinfunction "QH*_9") (pintype "tri_state"))
      (node (ref "IC6") (pin "14") (pinfunction "SER_14") (pintype "input"))
    )
    (net (code "28") (name "Net-(IC5-FB)") (class "Default")
      (node (ref "IC5") (pin "4") (pinfunction "FB_4") (pintype "bidirectional"))
      (node (ref "R34") (pin "1") (pinfunction "1_1") (pintype "passive"))
      (node (ref "R35") (pin "1") (pinfunction "1_1") (pintype "passive"))
    )
    (net (code "29") (name "Net-(IC6A-QA)") (class "Default")
      (node (ref "IC6") (pin "15") (pinfunction "QA_15") (pintype "tri_state"))
      (node (ref "R25") (pin "2") (pinfunction "2_2") (pintype "passive"))
    )
    (net (code "30") (name "Net-(IC6A-QB)") (class "Default")
      (node (ref "IC6") (pin "1") (pinfunction "QB_1") (pintype "tri_state"))
      (node (ref "R26") (pin "2") (pinfunction "2_2") (pintype "passive"))
    )
    (net (code "31") (name "Net-(IC6A-QC)") (class "Default")
      (node (ref "IC6") (pin "2") (pinfunction "QC_2") (pintype "tri_state"))
      (node (ref "R27") (pin "2") (pinfunction "2_2") (pintype "passive"))
    )
    (net (code "32") (name "Net-(IC6A-QD)") (class "Default")
      (node (ref "IC6") (pin "3") (pinfunction "QD_3") (pintype "tri_state"))
      (node (ref "R28") (pin "2") (pinfunction "2_2") (pintype "passive"))
    )
    (net (code "33") (name "Net-(IC6A-QE)") (class "Default")
      (node (ref "IC6") (pin "4") (pinfunction "QE_4") (pintype "tri_state"))
      (node (ref "R29") (pin "2") (pinfunction "2_2") (pintype "passive"))
    )
    (net (code "34") (name "Net-(IC6A-QF)") (class "Default")
      (node (ref "IC6") (pin "5") (pinfunction "QF_5") (pintype "tri_state"))
      (node (ref "R40") (pin "2") (pinfunction "2_2") (pintype "passive"))
    )
    (net (code "35") (name "Net-(IC6A-QG)") (class "Default")
      (node (ref "IC6") (pin "6") (pinfunction "QG_6") (pintype "tri_state"))
      (node (ref "R41") (pin "2") (pinfunction "2_2") (pintype "passive"))
    )
    (net (code "36") (name "Net-(IC6A-QH)") (class "Default")
      (node (ref "IC6") (pin "7") (pinfunction "QH_7") (pintype "tri_state"))
      (node (ref "R42") (pin "2") (pinfunction "2_2") (pintype "passive"))
    )
    (net (code "37") (name "Net-(IC6A-QH*)") (class "Default")
      (node (ref "IC6") (pin "9") (pinfunction "QH*_9") (pintype "tri_state"))
      (node (ref "IC7") (pin "14") (pinfunction "SER_14") (pintype "input"))
    )
    (net (code "38") (name "Net-(IC7A-QA)") (class "Default")
      (node (ref "IC7") (pin "15") (pinfunction "QA_15") (pintype "tri_state"))
      (node (ref "R43") (pin "2") (pinfunction "2_2") (pintype "passive"))
    )
    (net (code "39") (name "Net-(IC7A-QB)") (class "Default")
      (node (ref "IC7") (pin "1") (pinfunction "QB_1") (pintype "tri_state"))
      (node (ref "R44") (pin "2") (pinfunction "2_2") (pintype "passive"))
    )
    (net (code "40") (name "Net-(IC7A-QC)") (class "Default")
      (node (ref "IC7") (pin "2") (pinfunction "QC_2") (pintype "tri_state"))
      (node (ref "R45") (pin "2") (pinfunction "2_2") (pintype "passive"))
    )
    (net (code "41") (name "Net-(IC7A-QD)") (class "Default")
      (node (ref "IC7") (pin "3") (pinfunction "QD_3") (pintype "tri_state"))
      (node (ref "R46") (pin "2") (pinfunction "2_2") (pintype "passive"))
    )
    (net (code "42") (name "Net-(IC7A-QE)") (class "Default")
      (node (ref "IC7") (pin "4") (pinfunction "QE_4") (pintype "tri_state"))
      (node (ref "R47") (pin "2") (pinfunction "2_2") (pintype "passive"))
    )
    (net (code "43") (name "Net-(IC7A-QF)") (class "Default")
      (node (ref "IC7") (pin "5") (pinfunction "QF_5") (pintype "tri_state"))
      (node (ref "R48") (pin "2") (pinfunction "2_2") (pintype "passive"))
    )
    (net (code "44") (name "Net-(IC7A-QG)") (class "Default")
      (node (ref "IC7") (pin "6") (pinfunction "QG_6") (pintype "tri_state"))
      (node (ref "R49") (pin "2") (pinfunction "2_2") (pintype "passive"))
    )
    (net (code "45") (name "Net-(IC7A-QH)") (class "Default")
      (node (ref "IC7") (pin "7") (pinfunction "QH_7") (pintype "tri_state"))
      (node (ref "R50") (pin "2") (pinfunction "2_2") (pintype "passive"))
    )
    (net (code "46") (name "Net-(IC7A-QH*)") (class "Default")
      (node (ref "IC7") (pin "9") (pinfunction "QH*_9") (pintype "tri_state"))
      (node (ref "IC8") (pin "14") (pinfunction "SER_14") (pintype "input"))
    )
    (net (code "47") (name "Net-(IC8A-QA)") (class "Default")
      (node (ref "IC8") (pin "15") (pinfunction "QA_15") (pintype "tri_state"))
      (node (ref "R51") (pin "2") (pinfunction "2_2") (pintype "passive"))
    )
    (net (code "48") (name "Net-(IC8A-QB)") (class "Default")
      (node (ref "IC8") (pin "1") (pinfunction "QB_1") (pintype "tri_state"))
      (node (ref "R52") (pin "2") (pinfunction "2_2") (pintype "passive"))
    )
    (net (code "49") (name "Net-(IC8A-QC)") (class "Default")
      (node (ref "IC8") (pin "2") (pinfunction "QC_2") (pintype "tri_state"))
      (node (ref "R53") (pin "2") (pinfunction "2_2") (pintype "passive"))
    )
    (net (code "50") (name "Net-(IC8A-QD)") (class "Default")
      (node (ref "IC8") (pin "3") (pinfunction "QD_3") (pintype "tri_state"))
      (node (ref "R54") (pin "2") (pinfunction "2_2") (pintype "passive"))
    )
    (net (code "51") (name "Net-(IC8A-QE)") (class "Default")
      (node (ref "IC8") (pin "4") (pinfunction "QE_4") (pintype "tri_state"))
      (node (ref "R55") (pin "2") (pinfunction "2_2") (pintype "passive"))
    )
    (net (code "52") (name "Net-(IC8A-QF)") (class "Default")
      (node (ref "IC8") (pin "5") (pinfunction "QF_5") (pintype "tri_state"))
      (node (ref "R56") (pin "2") (pinfunction "2_2") (pintype "passive"))
    )
    (net (code "53") (name "Net-(IC8A-QG)") (class "Default")
      (node (ref "IC8") (pin "6") (pinfunction "QG_6") (pintype "tri_state"))
      (node (ref "R57") (pin "2") (pinfunction "2_2") (pintype "passive"))
    )
    (net (code "54") (name "Net-(IC8A-QH)") (class "Default")
      (node (ref "IC8") (pin "7") (pinfunction "QH_7") (pintype "tri_state"))
      (node (ref "R58") (pin "2") (pinfunction "2_2") (pintype "passive"))
    )
    (net (code "55") (name "Net-(IC8A-QH*)") (class "Default")
      (node (ref "IC8") (pin "9") (pinfunction "QH*_9") (pintype "tri_state"))
      (node (ref "R7") (pin "1") (pinfunction "1_1") (pintype "passive"))
    )
    (net (code "56") (name "Net-(JP2-1)") (class "Default")
      (node (ref "JP2") (pin "11") (pinfunction "1_11") (pintype "passive"))
      (node (ref "T1") (pin "3") (pinfunction "C_3") (pintype "passive"))
    )
    (net (code "57") (name "Net-(JP2-2)") (class "Default")
      (node (ref "JP2") (pin "12") (pinfunction "2_12") (pintype "passive"))
      (node (ref "T2") (pin "3") (pinfunction "C_3") (pintype "passive"))
    )
    (net (code "58") (name "Net-(JP2-3)") (class "Default")
      (node (ref "JP2") (pin "13") (pinfunction "3_13") (pintype "passive"))
      (node (ref "T3") (pin "3") (pinfunction "C_3") (pintype "passive"))
    )
    (net (code "59") (name "Net-(JP2-4)") (class "Default")
      (node (ref "JP2") (pin "14") (pinfunction "4_14") (pintype "passive"))
      (node (ref "T4") (pin "3") (pinfunction "C_3") (pintype "passive"))
    )
    (net (code "60") (name "Net-(JP2-5)") (class "Default")
      (node (ref "JP2") (pin "15") (pinfunction "5_15") (pintype "passive"))
      (node (ref "T5") (pin "3") (pinfunction "C_3") (pintype "passive"))
    )
    (net (code "61") (name "Net-(JP2-6)") (class "Default")
      (node (ref "JP2") (pin "16") (pinfunction "6_16") (pintype "passive"))
      (node (ref "T6") (pin "3") (pinfunction "C_3") (pintype "passive"))
    )
    (net (code "62") (name "Net-(JP2-7)") (class "Default")
      (node (ref "JP2") (pin "17") (pinfunction "7_17") (pintype "passive"))
      (node (ref "T7") (pin "3") (pinfunction "C_3") (pintype "passive"))
    )
    (net (code "63") (name "Net-(JP2-8)") (class "Default")
      (node (ref "JP2") (pin "18") (pinfunction "8_18") (pintype "passive"))
      (node (ref "T8") (pin "3") (pinfunction "C_3") (pintype "passive"))
    )
    (net (code "64") (name "Net-(JP2-9)") (class "Default")
      (node (ref "JP2") (pin "19") (pinfunction "9_19") (pintype "passive"))
      (node (ref "T9") (pin "3") (pinfunction "C_3") (pintype "passive"))
    )
    (net (code "65") (name "Net-(JP2-10)") (class "Default")
      (node (ref "JP2") (pin "20") (pinfunction "10_20") (pintype "passive"))
      (node (ref "T10") (pin "3") (pinfunction "C_3") (pintype "passive"))
    )
    (net (code "66") (name "Net-(JP3-1)") (class "Default")
      (node (ref "JP3") (pin "11") (pinfunction "1_11") (pintype "passive"))
      (node (ref "T11") (pin "3") (pinfunction "C_3") (pintype "passive"))
    )
    (net (code "67") (name "Net-(JP3-2)") (class "Default")
      (node (ref "JP3") (pin "12") (pinfunction "2_12") (pintype "passive"))
      (node (ref "T12") (pin "3") (pinfunction "C_3") (pintype "passive"))
    )
    (net (code "68") (name "Net-(JP3-3)") (class "Default")
      (node (ref "JP3") (pin "13") (pinfunction "3_13") (pintype "passive"))
      (node (ref "T13") (pin "3") (pinfunction "C_3") (pintype "passive"))
    )
    (net (code "69") (name "Net-(JP3-4)") (class "Default")
      (node (ref "JP3") (pin "14") (pinfunction "4_14") (pintype "passive"))
      (node (ref "T14") (pin "3") (pinfunction "C_3") (pintype "passive"))
    )
    (net (code "70") (name "Net-(JP3-5)") (class "Default")
      (node (ref "JP3") (pin "15") (pinfunction "5_15") (pintype "passive"))
      (node (ref "T15") (pin "3") (pinfunction "C_3") (pintype "passive"))
    )
    (net (code "71") (name "Net-(JP3-6)") (class "Default")
      (node (ref "JP3") (pin "16") (pinfunction "6_16") (pintype "passive"))
      (node (ref "T16") (pin "3") (pinfunction "C_3") (pintype "passive"))
    )
    (net (code "72") (name "Net-(JP3-7)") (class "Default")
      (node (ref "JP3") (pin "17") (pinfunction "7_17") (pintype "passive"))
      (node (ref "T17") (pin "3") (pinfunction "C_3") (pintype "passive"))
    )
    (net (code "73") (name "Net-(JP3-8)") (class "Default")
      (node (ref "JP3") (pin "18") (pinfunction "8_18") (pintype "passive"))
      (node (ref "T18") (pin "3") (pinfunction "C_3") (pintype "passive"))
    )
    (net (code "74") (name "Net-(JP3-9)") (class "Default")
      (node (ref "JP3") (pin "19") (pinfunction "9_19") (pintype "passive"))
      (node (ref "T19") (pin "3") (pinfunction "C_3") (pintype "passive"))
    )
    (net (code "75") (name "Net-(JP3-10)") (class "Default")
      (node (ref "JP3") (pin "20") (pinfunction "10_20") (pintype "passive"))
      (node (ref "T20") (pin "3") (pinfunction "C_3") (pintype "passive"))
    )
    (net (code "76") (name "Net-(JP4-1)") (class "Default")
      (node (ref "JP4") (pin "11") (pinfunction "1_11") (pintype "passive"))
      (node (ref "T21") (pin "3") (pinfunction "C_3") (pintype "passive"))
    )
    (net (code "77") (name "Net-(JP4-2)") (class "Default")
      (node (ref "JP4") (pin "12") (pinfunction "2_12") (pintype "passive"))
      (node (ref "T32") (pin "3") (pinfunction "C_3") (pintype "passive"))
    )
    (net (code "78") (name "Net-(JP4-3)") (class "Default")
      (node (ref "JP4") (pin "13") (pinfunction "3_13") (pintype "passive"))
      (node (ref "T33") (pin "3") (pinfunction "C_3") (pintype "passive"))
    )
    (net (code "79") (name "Net-(JP4-4)") (class "Default")
      (node (ref "JP4") (pin "14") (pinfunction "4_14") (pintype "passive"))
      (node (ref "T34") (pin "3") (pinfunction "C_3") (pintype "passive"))
    )
    (net (code "80") (name "Net-(JP4-5)") (class "Default")
      (node (ref "JP4") (pin "15") (pinfunction "5_15") (pintype "passive"))
      (node (ref "T35") (pin "3") (pinfunction "C_3") (pintype "passive"))
    )
    (net (code "81") (name "Net-(JP4-6)") (class "Default")
      (node (ref "JP4") (pin "16") (pinfunction "6_16") (pintype "passive"))
      (node (ref "T36") (pin "3") (pinfunction "C_3") (pintype "passive"))
    )
    (net (code "82") (name "Net-(JP4-7)") (class "Default")
      (node (ref "JP4") (pin "17") (pinfunction "7_17") (pintype "passive"))
      (node (ref "T37") (pin "3") (pinfunction "C_3") (pintype "passive"))
    )
    (net (code "83") (name "Net-(JP4-8)") (class "Default")
      (node (ref "JP4") (pin "18") (pinfunction "8_18") (pintype "passive"))
      (node (ref "T38") (pin "3") (pinfunction "C_3") (pintype "passive"))
    )
    (net (code "84") (name "Net-(JP4-9)") (class "Default")
      (node (ref "JP4") (pin "19") (pinfunction "9_19") (pintype "passive"))
      (node (ref "T39") (pin "3") (pinfunction "C_3") (pintype "passive"))
    )
    (net (code "85") (name "Net-(JP4-10)") (class "Default")
      (node (ref "JP4") (pin "20") (pinfunction "10_20") (pintype "passive"))
      (node (ref "T40") (pin "3") (pinfunction "C_3") (pintype "passive"))
    )
    (net (code "86") (name "Net-(JP5-1)") (class "Default")
      (node (ref "JP5") (pin "11") (pinfunction "1_11") (pintype "passive"))
      (node (ref "T41") (pin "3") (pinfunction "C_3") (pintype "passive"))
    )
    (net (code "87") (name "Net-(JP5-2)") (class "Default")
      (node (ref "JP5") (pin "12") (pinfunction "2_12") (pintype "passive"))
      (node (ref "T42") (pin "3") (pinfunction "C_3") (pintype "passive"))
    )
    (net (code "88") (name "Net-(JP5-3)") (class "Default")
      (node (ref "JP5") (pin "13") (pinfunction "3_13") (pintype "passive"))
      (node (ref "T43") (pin "3") (pinfunction "C_3") (pintype "passive"))
    )
    (net (code "89") (name "Net-(JP5-4)") (class "Default")
      (node (ref "JP5") (pin "14") (pinfunction "4_14") (pintype "passive"))
      (node (ref "T44") (pin "3") (pinfunction "C_3") (pintype "passive"))
    )
    (net (code "90") (name "Net-(JP5-5)") (class "Default")
      (node (ref "JP5") (pin "15") (pinfunction "5_15") (pintype "passive"))
      (node (ref "T45") (pin "3") (pinfunction "C_3") (pintype "passive"))
    )
    (net (code "91") (name "Net-(JP5-6)") (class "Default")
      (node (ref "JP5") (pin "16") (pinfunction "6_16") (pintype "passive"))
      (node (ref "T46") (pin "3") (pinfunction "C_3") (pintype "passive"))
    )
    (net (code "92") (name "Net-(JP5-7)") (class "Default")
      (node (ref "JP5") (pin "17") (pinfunction "7_17") (pintype "passive"))
      (node (ref "T47") (pin "3") (pinfunction "C_3") (pintype "passive"))
    )
    (net (code "93") (name "Net-(JP5-8)") (class "Default")
      (node (ref "JP5") (pin "18") (pinfunction "8_18") (pintype "passive"))
      (node (ref "T48") (pin "3") (pinfunction "C_3") (pintype "passive"))
    )
    (net (code "94") (name "Net-(JP5-9)") (class "Default")
      (node (ref "JP5") (pin "19") (pinfunction "9_19") (pintype "passive"))
      (node (ref "T49") (pin "3") (pinfunction "C_3") (pintype "passive"))
    )
    (net (code "95") (name "Net-(JP5-10)") (class "Default")
      (node (ref "JP5") (pin "20") (pinfunction "10_20") (pintype "passive"))
      (node (ref "T50") (pin "3") (pinfunction "C_3") (pintype "passive"))
    )
    (net (code "96") (name "Net-(LED2-PadA)") (class "Default")
      (node (ref "LED2") (pin "A") (pinfunction "A_A") (pintype "passive"))
      (node (ref "R7") (pin "2") (pinfunction "2_2") (pintype "passive"))
    )
    (net (code "97") (name "Net-(T1-B)") (class "Default")
      (node (ref "R9") (pin "1") (pinfunction "1_1") (pintype "passive"))
      (node (ref "T1") (pin "1") (pinfunction "B_1") (pintype "passive"))
    )
    (net (code "98") (name "Net-(T2-B)") (class "Default")
      (node (ref "R10") (pin "1") (pinfunction "1_1") (pintype "passive"))
      (node (ref "T2") (pin "1") (pinfunction "B_1") (pintype "passive"))
    )
    (net (code "99") (name "Net-(T3-B)") (class "Default")
      (node (ref "R11") (pin "1") (pinfunction "1_1") (pintype "passive"))
      (node (ref "T3") (pin "1") (pinfunction "B_1") (pintype "passive"))
    )
    (net (code "100") (name "Net-(T4-B)") (class "Default")
      (node (ref "R12") (pin "1") (pinfunction "1_1") (pintype "passive"))
      (node (ref "T4") (pin "1") (pinfunction "B_1") (pintype "passive"))
    )
    (net (code "101") (name "Net-(T5-B)") (class "Default")
      (node (ref "R13") (pin "1") (pinfunction "1_1") (pintype "passive"))
      (node (ref "T5") (pin "1") (pinfunction "B_1") (pintype "passive"))
    )
    (net (code "102") (name "Net-(T6-B)") (class "Default")
      (node (ref "R14") (pin "1") (pinfunction "1_1") (pintype "passive"))
      (node (ref "T6") (pin "1") (pinfunction "B_1") (pintype "passive"))
    )
    (net (code "103") (name "Net-(T7-B)") (class "Default")
      (node (ref "R15") (pin "1") (pinfunction "1_1") (pintype "passive"))
      (node (ref "T7") (pin "1") (pinfunction "B_1") (pintype "passive"))
    )
    (net (code "104") (name "Net-(T8-B)") (class "Default")
      (node (ref "R16") (pin "1") (pinfunction "1_1") (pintype "passive"))
      (node (ref "T8") (pin "1") (pinfunction "B_1") (pintype "passive"))
    )
    (net (code "105") (name "Net-(T9-B)") (class "Default")
      (node (ref "R17") (pin "1") (pinfunction "1_1") (pintype "passive"))
      (node (ref "T9") (pin "1") (pinfunction "B_1") (pintype "passive"))
    )
    (net (code "106") (name "Net-(T10-B)") (class "Default")
      (node (ref "R18") (pin "1") (pinfunction "1_1") (pintype "passive"))
      (node (ref "T10") (pin "1") (pinfunction "B_1") (pintype "passive"))
    )
    (net (code "107") (name "Net-(T11-B)") (class "Default")
      (node (ref "R19") (pin "1") (pinfunction "1_1") (pintype "passive"))
      (node (ref "T11") (pin "1") (pinfunction "B_1") (pintype "passive"))
    )
    (net (code "108") (name "Net-(T12-B)") (class "Default")
      (node (ref "R20") (pin "1") (pinfunction "1_1") (pintype "passive"))
      (node (ref "T12") (pin "1") (pinfunction "B_1") (pintype "passive"))
    )
    (net (code "109") (name "Net-(T13-B)") (class "Default")
      (node (ref "R21") (pin "1") (pinfunction "1_1") (pintype "passive"))
      (node (ref "T13") (pin "1") (pinfunction "B_1") (pintype "passive"))
    )
    (net (code "110") (name "Net-(T14-B)") (class "Default")
      (node (ref "R22") (pin "1") (pinfunction "1_1") (pintype "passive"))
      (node (ref "T14") (pin "1") (pinfunction "B_1") (pintype "passive"))
    )
    (net (code "111") (name "Net-(T15-B)") (class "Default")
      (node (ref "R23") (pin "1") (pinfunction "1_1") (pintype "passive"))
      (node (ref "T15") (pin "1") (pinfunction "B_1") (pintype "passive"))
    )
    (net (code "112") (name "Net-(T16-B)") (class "Default")
      (node (ref "R24") (pin "1") (pinfunction "1_1") (pintype "passive"))
      (node (ref "T16") (pin "1") (pinfunction "B_1") (pintype "passive"))
    )
    (net (code "113") (name "Net-(T17-B)") (class "Default")
      (node (ref "R25") (pin "1") (pinfunction "1_1") (pintype "passive"))
      (node (ref "T17") (pin "1") (pinfunction "B_1") (pintype "passive"))
    )
    (net (code "114") (name "Net-(T18-B)") (class "Default")
      (node (ref "R26") (pin "1") (pinfunction "1_1") (pintype "passive"))
      (node (ref "T18") (pin "1") (pinfunction "B_1") (pintype "passive"))
    )
    (net (code "115") (name "Net-(T19-B)") (class "Default")
      (node (ref "R27") (pin "1") (pinfunction "1_1") (pintype "passive"))
      (node (ref "T19") (pin "1") (pinfunction "B_1") (pintype "passive"))
    )
    (net (code "116") (name "Net-(T20-B)") (class "Default")
      (node (ref "R28") (pin "1") (pinfunction "1_1") (pintype "passive"))
      (node (ref "T20") (pin "1") (pinfunction "B_1") (pintype "passive"))
    )
    (net (code "117") (name "Net-(T21-B)") (class "Default")
      (node (ref "R29") (pin "1") (pinfunction "1_1") (pintype "passive"))
      (node (ref "T21") (pin "1") (pinfunction "B_1") (pintype "passive"))
    )
    (net (code "118") (name "Net-(T32-B)") (class "Default")
      (node (ref "R40") (pin "1") (pinfunction "1_1") (pintype "passive"))
      (node (ref "T32") (pin "1") (pinfunction "B_1") (pintype "passive"))
    )
    (net (code "119") (name "Net-(T33-B)") (class "Default")
      (node (ref "R41") (pin "1") (pinfunction "1_1") (pintype "passive"))
      (node (ref "T33") (pin "1") (pinfunction "B_1") (pintype "passive"))
    )
    (net (code "120") (name "Net-(T34-B)") (class "Default")
      (node (ref "R42") (pin "1") (pinfunction "1_1") (pintype "passive"))
      (node (ref "T34") (pin "1") (pinfunction "B_1") (pintype "passive"))
    )
    (net (code "121") (name "Net-(T35-B)") (class "Default")
      (node (ref "R43") (pin "1") (pinfunction "1_1") (pintype "passive"))
      (node (ref "T35") (pin "1") (pinfunction "B_1") (pintype "passive"))
    )
    (net (code "122") (name "Net-(T36-B)") (class "Default")
      (node (ref "R44") (pin "1") (pinfunction "1_1") (pintype "passive"))
      (node (ref "T36") (pin "1") (pinfunction "B_1") (pintype "passive"))
    )
    (net (code "123") (name "Net-(T37-B)") (class "Default")
      (node (ref "R45") (pin "1") (pinfunction "1_1") (pintype "passive"))
      (node (ref "T37") (pin "1") (pinfunction "B_1") (pintype "passive"))
    )
    (net (code "124") (name "Net-(T38-B)") (class "Default")
      (node (ref "R46") (pin "1") (pinfunction "1_1") (pintype "passive"))
      (node (ref "T38") (pin "1") (pinfunction "B_1") (pintype "passive"))
    )
    (net (code "125") (name "Net-(T39-B)") (class "Default")
      (node (ref "R47") (pin "1") (pinfunction "1_1") (pintype "passive"))
      (node (ref "T39") (pin "1") (pinfunction "B_1") (pintype "passive"))
    )
    (net (code "126") (name "Net-(T40-B)") (class "Default")
      (node (ref "R48") (pin "1") (pinfunction "1_1") (pintype "passive"))
      (node (ref "T40") (pin "1") (pinfunction "B_1") (pintype "passive"))
    )
    (net (code "127") (name "Net-(T41-B)") (class "Default")
      (node (ref "R49") (pin "1") (pinfunction "1_1") (pintype "passive"))
      (node (ref "T41") (pin "1") (pinfunction "B_1") (pintype "passive"))
    )
    (net (code "128") (name "Net-(T42-B)") (class "Default")
      (node (ref "R50") (pin "1") (pinfunction "1_1") (pintype "passive"))
      (node (ref "T42") (pin "1") (pinfunction "B_1") (pintype "passive"))
    )
    (net (code "129") (name "Net-(T43-B)") (class "Default")
      (node (ref "R51") (pin "1") (pinfunction "1_1") (pintype "passive"))
      (node (ref "T43") (pin "1") (pinfunction "B_1") (pintype "passive"))
    )
    (net (code "130") (name "Net-(T44-B)") (class "Default")
      (node (ref "R52") (pin "1") (pinfunction "1_1") (pintype "passive"))
      (node (ref "T44") (pin "1") (pinfunction "B_1") (pintype "passive"))
    )
    (net (code "131") (name "Net-(T45-B)") (class "Default")
      (node (ref "R53") (pin "1") (pinfunction "1_1") (pintype "passive"))
      (node (ref "T45") (pin "1") (pinfunction "B_1") (pintype "passive"))
    )
    (net (code "132") (name "Net-(T46-B)") (class "Default")
      (node (ref "R54") (pin "1") (pinfunction "1_1") (pintype "passive"))
      (node (ref "T46") (pin "1") (pinfunction "B_1") (pintype "passive"))
    )
    (net (code "133") (name "Net-(T47-B)") (class "Default")
      (node (ref "R55") (pin "1") (pinfunction "1_1") (pintype "passive"))
      (node (ref "T47") (pin "1") (pinfunction "B_1") (pintype "passive"))
    )
    (net (code "134") (name "Net-(T48-B)") (class "Default")
      (node (ref "R56") (pin "1") (pinfunction "1_1") (pintype "passive"))
      (node (ref "T48") (pin "1") (pinfunction "B_1") (pintype "passive"))
    )
    (net (code "135") (name "Net-(T49-B)") (class "Default")
      (node (ref "R57") (pin "1") (pinfunction "1_1") (pintype "passive"))
      (node (ref "T49") (pin "1") (pinfunction "B_1") (pintype "passive"))
    )
    (net (code "136") (name "Net-(T50-B)") (class "Default")
      (node (ref "R58") (pin "1") (pinfunction "1_1") (pintype "passive"))
      (node (ref "T50") (pin "1") (pinfunction "B_1") (pintype "passive"))
    )
    (net (code "137") (name "Net-(X1-GPIO0)") (class "Default")
      (node (ref "JP6") (pin "2") (pinfunction "2_2") (pintype "passive"))
      (node (ref "R2") (pin "1") (pinfunction "1_1") (pintype "passive"))
      (node (ref "X1") (pin "12") (pinfunction "GPIO0_12") (pintype "bidirectional"))
    )
    (net (code "138") (name "Net-(X1-RESET)") (class "Default")
      (node (ref "C1") (pin "2") (pinfunction "2_2") (pintype "passive"))
      (node (ref "R1") (pin "1") (pinfunction "1_1") (pintype "passive"))
      (node (ref "X1") (pin "1") (pinfunction "RESET_1") (pintype "input"))
    )
    (net (code "139") (name "Net-(X1-RXD)") (class "Default")
      (node (ref "JP1") (pin "2") (pinfunction "2_2") (pintype "passive"))
      (node (ref "X1") (pin "15") (pinfunction "RXD_15") (pintype "input"))
    )
    (net (code "140") (name "Net-(X1-TXD)") (class "Default")
      (node (ref "JP1") (pin "1") (pinfunction "1_1") (pintype "passive"))
      (node (ref "X1") (pin "16") (pinfunction "TXD_16") (pintype "output"))
    )
    (net (code "141") (name "VCC") (class "Default")
      (node (ref "C10") (pin "2") (pinfunction "2_2") (pintype "passive"))
      (node (ref "C12") (pin "+") (pinfunction "+_+") (pintype "passive"))
      (node (ref "C2") (pin "2") (pinfunction "2_2") (pintype "passive"))
      (node (ref "C6") (pin "2") (pinfunction "2_2") (pintype "passive"))
      (node (ref "C7") (pin "2") (pinfunction "2_2") (pintype "passive"))
      (node (ref "C8") (pin "2") (pinfunction "2_2") (pintype "passive"))
      (node (ref "C9") (pin "2") (pinfunction "2_2") (pintype "passive"))
      (node (ref "IC1") (pin "10") (pinfunction "SCL_10") (pintype "input"))
      (node (ref "IC1") (pin "16") (pinfunction "VCC_16") (pintype "power_in"))
      (node (ref "IC2") (pin "10") (pinfunction "SCL_10") (pintype "input"))
      (node (ref "IC2") (pin "16") (pinfunction "VCC_16") (pintype "power_in"))
      (node (ref "IC6") (pin "10") (pinfunction "SCL_10") (pintype "input"))
      (node (ref "IC6") (pin "16") (pinfunction "VCC_16") (pintype "power_in"))
      (node (ref "IC7") (pin "10") (pinfunction "SCL_10") (pintype "input"))
      (node (ref "IC7") (pin "16") (pinfunction "VCC_16") (pintype "power_in"))
      (node (ref "IC8") (pin "10") (pinfunction "SCL_10") (pintype "input"))
      (node (ref "IC8") (pin "16") (pinfunction "VCC_16") (pintype "power_in"))
      (node (ref "L1") (pin "1") (pinfunction "1_1") (pintype "passive"))
      (node (ref "R1") (pin "2") (pinfunction "2_2") (pintype "passive"))
      (node (ref "R2") (pin "2") (pinfunction "2_2") (pintype "passive"))
      (node (ref "R35") (pin "2") (pinfunction "2_2") (pintype "passive"))
      (node (ref "VCC") (pin "1") (pinfunction "P_1") (pintype "passive"))
      (node (ref "X1") (pin "3") (pinfunction "CH_PD_3") (pintype "input"))
      (node (ref "X1") (pin "8") (pinfunction "VCC_8") (pintype "power_in"))
    )
    (net (code "142") (name "unconnected-(X1-ADC-Pad2)") (class "Default")
      (node (ref "X1") (pin "2") (pinfunction "ADC_2") (pintype "passive"))
    )
    (net (code "143") (name "unconnected-(X1-GPIO2-Pad11)") (class "Default")
      (node (ref "X1") (pin "11") (pinfunction "GPIO2_11") (pintype "bidirectional"))
    )
    (net (code "144") (name "unconnected-(X1-GPIO4-Pad14)") (class "Default")
      (node (ref "X1") (pin "14") (pinfunction "GPIO4_14") (pintype "bidirectional"))
    )
    (net (code "145") (name "unconnected-(X1-GPIO5-Pad13)") (class "Default")
      (node (ref "X1") (pin "13") (pinfunction "GPIO5_13") (pintype "bidirectional"))
    )
    (net (code "146") (name "unconnected-(X1-GPIO13-Pad7)") (class "Default")
      (node (ref "X1") (pin "7") (pinfunction "GPIO13_7") (pintype "bidirectional"))
    )
    (net (code "147") (name "unconnected-(X1-GPIO15-Pad10)") (class "Default")
      (node (ref "X1") (pin "10") (pinfunction "GPIO15_10") (pintype "bidirectional"))
    )
  )
)
